# C5_Running_indicators.net
KiCad netlist of a schematic drawn in EAGLE
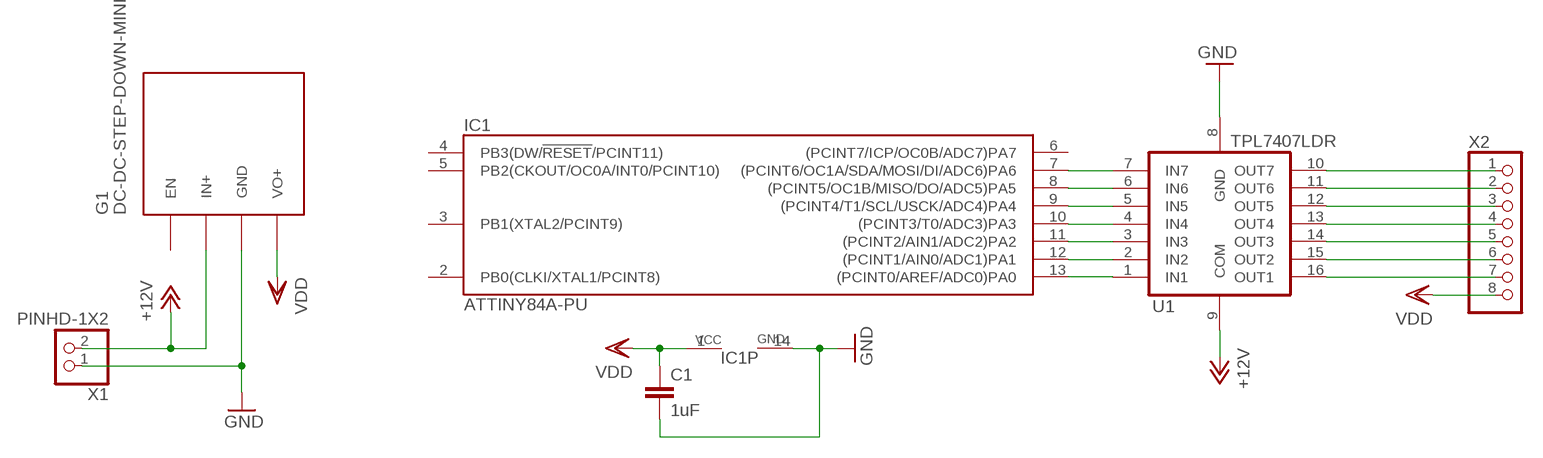
[diagram p0: schematic, sheet 1]

(export (version "E")
  (design (tool "Eeschema 10.0.6"))
  (components
    (comp (ref "C1")
      (value "1uF")
      (footprint "eagle-import:C050-025X075")
      (libsource (lib "eagle-import") (part "C-EU050-025X075"))
    )
    (comp (ref "G1")
      (value "DC-DC-STEP-DOWN-MINI")
      (footprint "eagle-import:DC-DC-DOWN-MINI")
      (libsource (lib "eagle-import") (part "DC-DC-STEP-DOWN-MINI"))
    )
    (comp (ref "IC1")
      (value "ATTINY84A-PU")
      (footprint "eagle-import:DIL14")
      (libsource (lib "eagle-import") (part "ATTINY4A-PU8"))
    )
    (comp (ref "U1")
      (value "TPL7407LDR")
      (footprint "eagle-import:SOIC16N")
      (libsource (lib "eagle-import") (part "TPL7407LDR"))
    )
    (comp (ref "X1")
      (value "PINHD-1X2")
      (footprint "eagle-import:1X02")
      (libsource (lib "eagle-import") (part "PINHD-1X2"))
    )
    (comp (ref "X2")
      (value "PINHD-1X8")
      (footprint "eagle-import:1X08")
      (libsource (lib "eagle-import") (part "PINHD-1X8"))
    )
  )
  (nets
    (net (code "1") (name "+12V") (class "Default")
      (node (ref "G1") (pin "2") (pinfunction "IN+_2") (pintype "bidirectional"))
      (node (ref "U1") (pin "9") (pinfunction "COM_9") (pintype "power_in"))
      (node (ref "X1") (pin "2") (pinfunction "2_2") (pintype "passive"))
    )
    (net (code "2") (name "GND") (class "Default")
      (node (ref "C1") (pin "2") (pinfunction "2_2") (pintype "passive"))
      (node (ref "G1") (pin "3") (pinfunction "GND_3") (pintype "bidirectional"))
      (node (ref "IC1") (pin "14") (pinfunction "GND_14") (pintype "power_in"))
      (node (ref "U1") (pin "8") (pinfunction "GND_8") (pintype "power_in"))
      (node (ref "X1") (pin "1") (pinfunction "1_1") (pintype "passive"))
    )
    (net (code "3") (name "Net-(IC1A-(PCINT0{slash}AREF{slash}ADC0)PA0)") (class "Default")
      (node (ref "IC1") (pin "13") (pinfunction "(PCINT0/AREF/ADC0)PA0_13") (pintype "bidirectional"))
      (node (ref "U1") (pin "1") (pinfunction "IN1_1") (pintype "input"))
    )
    (net (code "4") (name "Net-(IC1A-(PCINT1{slash}AIN0{slash}ADC1)PA1)") (class "Default")
      (node (ref "IC1") (pin "12") (pinfunction "(PCINT1/AIN0/ADC1)PA1_12") (pintype "bidirectional"))
      (node (ref "U1") (pin "2") (pinfunction "IN2_2") (pintype "input"))
    )
    (net (code "5") (name "Net-(IC1A-(PCINT2{slash}AIN1{slash}ADC2)PA2)") (class "Default")
      (node (ref "IC1") (pin "11") (pinfunction "(PCINT2/AIN1/ADC2)PA2_11") (pintype "bidirectional"))
      (node (ref "U1") (pin "3") (pinfunction "IN3_3") (pintype "input"))
    )
    (net (code "6") (name "Net-(IC1A-(PCINT3{slash}T0{slash}ADC3)PA3)") (class "Default")
      (node (ref "IC1") (pin "10") (pinfunction "(PCINT3/T0/ADC3)PA3_10") (pintype "bidirectional"))
      (node (ref "U1") (pin "4") (pinfunction "IN4_4") (pintype "input"))
    )
    (net (code "7") (name "Net-(IC1A-(PCINT4{slash}T1{slash}SCL{slash}USCK{slash}ADC4)PA4)") (class "Default")
      (node (ref "IC1") (pin "9") (pinfunction "(PCINT4/T1/SCL/USCK/ADC4)PA4_9") (pintype "bidirectional"))
      (node (ref "U1") (pin "5") (pinfunction "IN5_5") (pintype "input"))
    )
    (net (code "8") (name "Net-(IC1A-(PCINT5{slash}OC1B{slash}MISO{slash}DO{slash}ADC5)PA5)") (class "Default")
      (node (ref "IC1") (pin "8") (pinfunction "(PCINT5/OC1B/MISO/DO/ADC5)PA5_8") (pintype "bidirectional"))
      (node (ref "U1") (pin "6") (pinfunction "IN6_6") (pintype "input"))
    )
    (net (code "9") (name "Net-(IC1A-(PCINT6{slash}OC1A{slash}SDA{slash}MOSI{slash}DI{slash}ADC6)PA6)") (class "Default")
      (node (ref "IC1") (pin "7") (pinfunction "(PCINT6/OC1A/SDA/MOSI/DI/ADC6)PA6_7") (pintype "bidirectional"))
      (node (ref "U1") (pin "7") (pinfunction "IN7_7") (pintype "input"))
    )
    (net (code "10") (name "Net-(U1-OUT1)") (class "Default")
      (node (ref "U1") (pin "16") (pinfunction "OUT1_16") (pintype "output"))
      (node (ref "X2") (pin "7") (pinfunction "7_7") (pintype "passive"))
    )
    (net (code "11") (name "Net-(U1-OUT2)") (class "Default")
      (node (ref "U1") (pin "15") (pinfunction "OUT2_15") (pintype "output"))
      (node (ref "X2") (pin "6") (pinfunction "6_6") (pintype "passive"))
    )
    (net (code "12") (name "Net-(U1-OUT3)") (class "Default")
      (node (ref "U1") (pin "14") (pinfunction "OUT3_14") (pintype "output"))
      (node (ref "X2") (pin "5") (pinfunction "5_5") (pintype "passive"))
    )
    (net (code "13") (name "Net-(U1-OUT4)") (class "Default")
      (node (ref "U1") (pin "13") (pinfunction "OUT4_13") (pintype "output"))
      (node (ref "X2") (pin "4") (pinfunction "4_4") (pintype "passive"))
    )
    (net (code "14") (name "Net-(U1-OUT5)") (class "Default")
      (node (ref "U1") (pin "12") (pinfunction "OUT5_12") (pintype "output"))
      (node (ref "X2") (pin "3") (pinfunction "3_3") (pintype "passive"))
    )
    (net (code "15") (name "Net-(U1-OUT6)") (class "Default")
      (node (ref "U1") (pin "11") (pinfunction "OUT6_11") (pintype "output"))
      (node (ref "X2") (pin "2") (pinfunction "2_2") (pintype "passive"))
    )
    (net (code "16") (name "Net-(U1-OUT7)") (class "Default")
      (node (ref "U1") (pin "10") (pinfunction "OUT7_10") (pintype "output"))
      (node (ref "X2") (pin "1") (pinfunction "1_1") (pintype "passive"))
    )
    (net (code "17") (name "VDD") (class "Default")
      (node (ref "C1") (pin "1") (pinfunction "1_1") (pintype "passive"))
      (node (ref "G1") (pin "4") (pinfunction "VO+_4") (pintype "bidirectional"))
      (node (ref "IC1") (pin "1") (pinfunction "VCC_1") (pintype "power_in"))
      (node (ref "X2") (pin "8") (pinfunction "8_8") (pintype "passive"))
    )
    (net (code "18") (name "unconnected-(G1-EN-Pad1)") (class "Default")
      (node (ref "G1") (pin "1") (pinfunction "EN_1") (pintype "bidirectional"))
    )
    (net (code "19") (name "unconnected-(IC1A-(PCINT7{slash}ICP{slash}OC0B{slash}ADC7)PA7-Pad6)") (class "Default")
      (node (ref "IC1") (pin "6") (pinfunction "(PCINT7/ICP/OC0B/ADC7)PA7_6") (pintype "bidirectional"))
    )
    (net (code "20") (name "unconnected-(IC1A-PB0(CLKI{slash}XTAL1{slash}PCINT8)-Pad2)") (class "Default")
      (node (ref "IC1") (pin "2") (pinfunction "PB0(CLKI/XTAL1/PCINT8)_2") (pintype "bidirectional"))
    )
    (net (code "21") (name "unconnected-(IC1A-PB1(XTAL2{slash}PCINT9)-Pad3)") (class "Default")
      (node (ref "IC1") (pin "3") (pinfunction "PB1(XTAL2/PCINT9)_3") (pintype "bidirectional"))
    )
    (net (code "22") (name "unconnected-(IC1A-PB2(CKOUT{slash}OC0A{slash}INT0{slash}PCINT10)-Pad5)") (class "Default")
      (node (ref "IC1") (pin "5") (pinfunction "PB2(CKOUT/OC0A/INT0/PCINT10)_5") (pintype "bidirectional"))
    )
    (net (code "23") (name "unconnected-(IC1A-PB3(DW{slash}~{RESET}{slash}PCINT11)-Pad4)") (class "Default")
      (node (ref "IC1") (pin "4") (pinfunction "PB3(DW/~{RESET}/PCINT11)_4") (pintype "bidirectional"))
    )
  )
)
